# psu.net
KiCad netlist of a schematic drawn in EAGLE
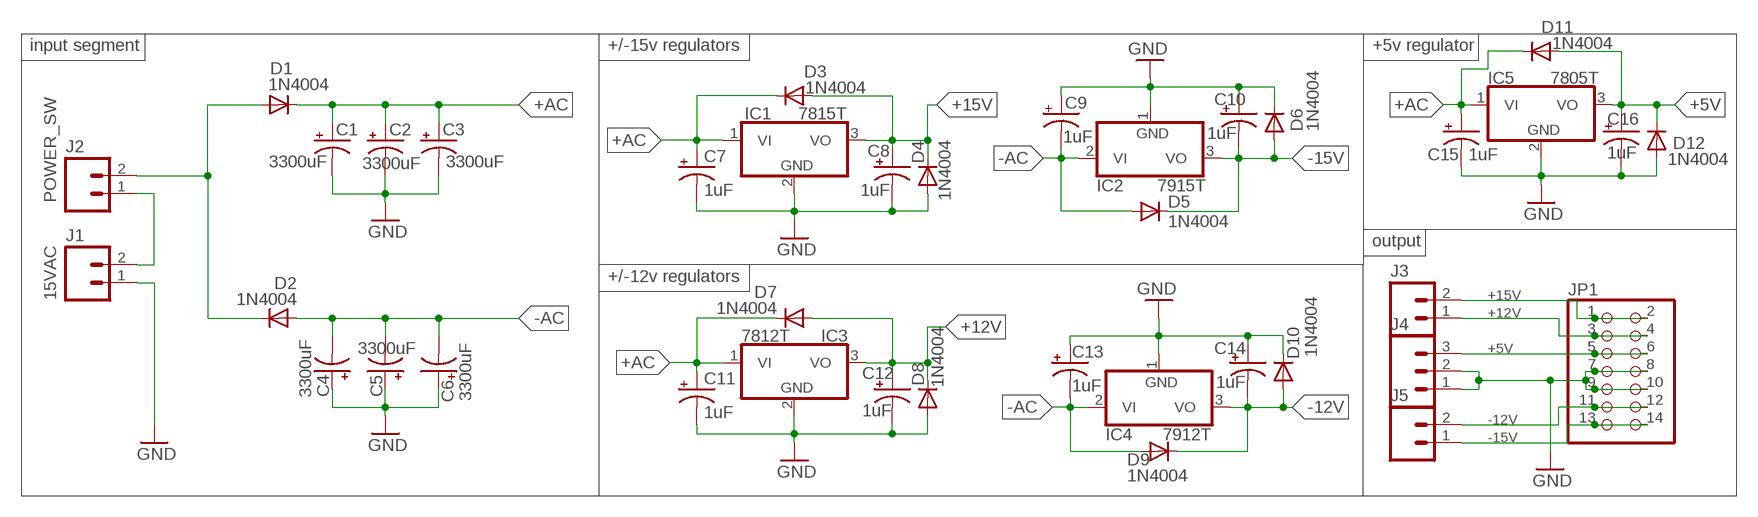
[diagram p0: schematic, sheet 1]

(export (version "E")
  (design (tool "Eeschema 10.0.6"))
  (components
    (comp (ref "C1")
      (value "3300uF")
      (footprint "eagle-import:E7,5-18")
      (libsource (lib "eagle-import") (part "CPOL-USE7.5-18"))
    )
    (comp (ref "C2")
      (value "3300uF")
      (footprint "eagle-import:E7,5-18")
      (libsource (lib "eagle-import") (part "CPOL-USE7.5-18"))
    )
    (comp (ref "C3")
      (value "3300uF")
      (footprint "eagle-import:E7,5-18")
      (libsource (lib "eagle-import") (part "CPOL-USE7.5-18"))
    )
    (comp (ref "C4")
      (value "3300uF")
      (footprint "eagle-import:E7,5-18")
      (libsource (lib "eagle-import") (part "CPOL-USE7.5-18"))
    )
    (comp (ref "C5")
      (value "3300uF")
      (footprint "eagle-import:E7,5-18")
      (libsource (lib "eagle-import") (part "CPOL-USE7.5-18"))
    )
    (comp (ref "C6")
      (value "3300uF")
      (footprint "eagle-import:E7,5-18")
      (libsource (lib "eagle-import") (part "CPOL-USE7.5-18"))
    )
    (comp (ref "C7")
      (value "1uF")
      (footprint "eagle-import:E2,5-5")
      (libsource (lib "eagle-import") (part "CPOL-USE2.5-5"))
    )
    (comp (ref "C8")
      (value "1uF")
      (footprint "eagle-import:E2,5-5")
      (libsource (lib "eagle-import") (part "CPOL-USE2.5-5"))
    )
    (comp (ref "C9")
      (value "1uF")
      (footprint "eagle-import:E2,5-5")
      (libsource (lib "eagle-import") (part "CPOL-USE2.5-5"))
    )
    (comp (ref "C10")
      (value "1uF")
      (footprint "eagle-import:E2,5-5")
      (libsource (lib "eagle-import") (part "CPOL-USE2.5-5"))
    )
    (comp (ref "C11")
      (value "1uF")
      (footprint "eagle-import:E2,5-5")
      (libsource (lib "eagle-import") (part "CPOL-USE2.5-5"))
    )
    (comp (ref "C12")
      (value "1uF")
      (footprint "eagle-import:E2,5-5")
      (libsource (lib "eagle-import") (part "CPOL-USE2.5-5"))
    )
    (comp (ref "C13")
      (value "1uF")
      (footprint "eagle-import:E2,5-5")
      (libsource (lib "eagle-import") (part "CPOL-USE2.5-5"))
    )
    (comp (ref "C14")
      (value "1uF")
      (footprint "eagle-import:E2,5-5")
      (libsource (lib "eagle-import") (part "CPOL-USE2.5-5"))
    )
    (comp (ref "C15")
      (value "1uF")
      (footprint "eagle-import:E2,5-5")
      (libsource (lib "eagle-import") (part "CPOL-USE2.5-5"))
    )
    (comp (ref "C16")
      (value "1uF")
      (footprint "eagle-import:E2,5-5")
      (libsource (lib "eagle-import") (part "CPOL-USE2.5-5"))
    )
    (comp (ref "D1")
      (value "1N4004")
      (footprint "eagle-import:DO41-10")
      (libsource (lib "eagle-import") (part "1N4004"))
    )
    (comp (ref "D2")
      (value "1N4004")
      (footprint "eagle-import:DO41-10")
      (libsource (lib "eagle-import") (part "1N4004"))
    )
    (comp (ref "D3")
      (value "1N4004")
      (footprint "eagle-import:DO41-10")
      (libsource (lib "eagle-import") (part "1N4004"))
    )
    (comp (ref "D4")
      (value "1N4004")
      (footprint "eagle-import:DO41-10")
      (libsource (lib "eagle-import") (part "1N4004"))
    )
    (comp (ref "D5")
      (value "1N4004")
      (footprint "eagle-import:DO41-10")
      (libsource (lib "eagle-import") (part "1N4004"))
    )
    (comp (ref "D6")
      (value "1N4004")
      (footprint "eagle-import:DO41-10")
      (libsource (lib "eagle-import") (part "1N4004"))
    )
    (comp (ref "D7")
      (value "1N4004")
      (footprint "eagle-import:DO41-10")
      (libsource (lib "eagle-import") (part "1N4004"))
    )
    (comp (ref "D8")
      (value "1N4004")
      (footprint "eagle-import:DO41-10")
      (libsource (lib "eagle-import") (part "1N4004"))
    )
    (comp (ref "D9")
      (value "1N4004")
      (footprint "eagle-import:DO41-10")
      (libsource (lib "eagle-import") (part "1N4004"))
    )
    (comp (ref "D10")
      (value "1N4004")
      (footprint "eagle-import:DO41-10")
      (libsource (lib "eagle-import") (part "1N4004"))
    )
    (comp (ref "D11")
      (value "1N4004")
      (footprint "eagle-import:DO41-10")
      (libsource (lib "eagle-import") (part "1N4004"))
    )
    (comp (ref "D12")
      (value "1N4004")
      (footprint "eagle-import:DO41-10")
      (libsource (lib "eagle-import") (part "1N4004"))
    )
    (comp (ref "IC1")
      (value "7815T")
      (footprint "eagle-import:TO220H")
      (libsource (lib "eagle-import") (part "78T15"))
    )
    (comp (ref "IC2")
      (value "7915T")
      (footprint "eagle-import:TO220H")
      (libsource (lib "eagle-import") (part "79T15"))
    )
    (comp (ref "IC3")
      (value "7812T")
      (footprint "eagle-import:TO220H")
      (libsource (lib "eagle-import") (part "78T12"))
    )
    (comp (ref "IC4")
      (value "7912T")
      (footprint "eagle-import:TO220H")
      (libsource (lib "eagle-import") (part "79T12"))
    )
    (comp (ref "IC5")
      (value "7805T")
      (footprint "eagle-import:TO220H")
      (libsource (lib "eagle-import") (part "78T05"))
    )
    (comp (ref "J1")
      (value "15VAC")
      (footprint "eagle-import:SCREWTERMINAL-5MM-2")
      (libsource (lib "eagle-import") (part "M025MM"))
    )
    (comp (ref "J2")
      (value "POWER_SW")
      (footprint "eagle-import:SCREWTERMINAL-5MM-2")
      (libsource (lib "eagle-import") (part "M025MM"))
    )
    (comp (ref "J3")
      (value "M025MM")
      (footprint "eagle-import:SCREWTERMINAL-5MM-2")
      (libsource (lib "eagle-import") (part "M025MM"))
    )
    (comp (ref "J4")
      (value "M03-SCREW-5MM")
      (footprint "eagle-import:SCREWTERMINAL-5MM-3")
      (libsource (lib "eagle-import") (part "M03-SCREW-5MM"))
    )
    (comp (ref "J5")
      (value "M025MM")
      (footprint "eagle-import:SCREWTERMINAL-5MM-2")
      (libsource (lib "eagle-import") (part "M025MM"))
    )
    (comp (ref "JP1")
      (value "PINHD-2X7")
      (footprint "eagle-import:2X07")
      (libsource (lib "eagle-import") (part "PINHD-2X7"))
    )
  )
  (nets
    (net (code "1") (name "+5V") (class "Default")
      (node (ref "C16") (pin "+") (pinfunction "+_+") (pintype "passive"))
      (node (ref "D11") (pin "A") (pinfunction "A_A") (pintype "passive"))
      (node (ref "D12") (pin "C") (pinfunction "C_C") (pintype "passive"))
      (node (ref "IC5") (pin "3") (pinfunction "VO_3") (pintype "passive"))
      (node (ref "J4") (pin "3") (pinfunction "3_3") (pintype "passive"))
      (node (ref "JP1") (pin "5") (pinfunction "5_5") (pintype "passive"))
      (node (ref "JP1") (pin "6") (pinfunction "6_6") (pintype "passive"))
    )
    (net (code "2") (name "+12V") (class "Default")
      (node (ref "C12") (pin "+") (pinfunction "+_+") (pintype "passive"))
      (node (ref "D7") (pin "A") (pinfunction "A_A") (pintype "passive"))
      (node (ref "D8") (pin "C") (pinfunction "C_C") (pintype "passive"))
      (node (ref "IC3") (pin "3") (pinfunction "VO_3") (pintype "passive"))
      (node (ref "J3") (pin "1") (pinfunction "1_1") (pintype "passive"))
      (node (ref "JP1") (pin "3") (pinfunction "3_3") (pintype "passive"))
      (node (ref "JP1") (pin "4") (pinfunction "4_4") (pintype "passive"))
    )
    (net (code "3") (name "+15V") (class "Default")
      (node (ref "C8") (pin "+") (pinfunction "+_+") (pintype "passive"))
      (node (ref "D3") (pin "A") (pinfunction "A_A") (pintype "passive"))
      (node (ref "D4") (pin "C") (pinfunction "C_C") (pintype "passive"))
      (node (ref "IC1") (pin "3") (pinfunction "VO_3") (pintype "passive"))
      (node (ref "J3") (pin "2") (pinfunction "2_2") (pintype "passive"))
      (node (ref "JP1") (pin "1") (pinfunction "1_1") (pintype "passive"))
      (node (ref "JP1") (pin "2") (pinfunction "2_2") (pintype "passive"))
    )
    (net (code "4") (name "+AC") (class "Default")
      (node (ref "C1") (pin "+") (pinfunction "+_+") (pintype "passive"))
      (node (ref "C11") (pin "+") (pinfunction "+_+") (pintype "passive"))
      (node (ref "C15") (pin "+") (pinfunction "+_+") (pintype "passive"))
      (node (ref "C2") (pin "+") (pinfunction "+_+") (pintype "passive"))
      (node (ref "C3") (pin "+") (pinfunction "+_+") (pintype "passive"))
      (node (ref "C7") (pin "+") (pinfunction "+_+") (pintype "passive"))
      (node (ref "D1") (pin "C") (pinfunction "C_C") (pintype "passive"))
      (node (ref "D11") (pin "C") (pinfunction "C_C") (pintype "passive"))
      (node (ref "D3") (pin "C") (pinfunction "C_C") (pintype "passive"))
      (node (ref "D7") (pin "C") (pinfunction "C_C") (pintype "passive"))
      (node (ref "IC1") (pin "1") (pinfunction "VI_1") (pintype "input"))
      (node (ref "IC3") (pin "1") (pinfunction "VI_1") (pintype "input"))
      (node (ref "IC5") (pin "1") (pinfunction "VI_1") (pintype "input"))
    )
    (net (code "5") (name "-12V") (class "Default")
      (node (ref "C14") (pin "-") (pinfunction "-_-") (pintype "passive"))
      (node (ref "D10") (pin "A") (pinfunction "A_A") (pintype "passive"))
      (node (ref "D9") (pin "C") (pinfunction "C_C") (pintype "passive"))
      (node (ref "IC4") (pin "3") (pinfunction "VO_3") (pintype "passive"))
      (node (ref "J5") (pin "2") (pinfunction "2_2") (pintype "passive"))
      (node (ref "JP1") (pin "11") (pinfunction "11_11") (pintype "passive"))
      (node (ref "JP1") (pin "12") (pinfunction "12_12") (pintype "passive"))
    )
    (net (code "6") (name "-15V") (class "Default")
      (node (ref "C10") (pin "-") (pinfunction "-_-") (pintype "passive"))
      (node (ref "D5") (pin "C") (pinfunction "C_C") (pintype "passive"))
      (node (ref "D6") (pin "A") (pinfunction "A_A") (pintype "passive"))
      (node (ref "IC2") (pin "3") (pinfunction "VO_3") (pintype "passive"))
      (node (ref "J5") (pin "1") (pinfunction "1_1") (pintype "passive"))
      (node (ref "JP1") (pin "13") (pinfunction "13_13") (pintype "passive"))
      (node (ref "JP1") (pin "14") (pinfunction "14_14") (pintype "passive"))
    )
    (net (code "7") (name "-AC") (class "Default")
      (node (ref "C13") (pin "-") (pinfunction "-_-") (pintype "passive"))
      (node (ref "C4") (pin "-") (pinfunction "-_-") (pintype "passive"))
      (node (ref "C5") (pin "-") (pinfunction "-_-") (pintype "passive"))
      (node (ref "C6") (pin "-") (pinfunction "-_-") (pintype "passive"))
      (node (ref "C9") (pin "-") (pinfunction "-_-") (pintype "passive"))
      (node (ref "D2") (pin "A") (pinfunction "A_A") (pintype "passive"))
      (node (ref "D5") (pin "A") (pinfunction "A_A") (pintype "passive"))
      (node (ref "D9") (pin "A") (pinfunction "A_A") (pintype "passive"))
      (node (ref "IC2") (pin "2") (pinfunction "VI_2") (pintype "input"))
      (node (ref "IC4") (pin "2") (pinfunction "VI_2") (pintype "input"))
    )
    (net (code "8") (name "GND") (class "Default")
      (node (ref "C1") (pin "-") (pinfunction "-_-") (pintype "passive"))
      (node (ref "C10") (pin "+") (pinfunction "+_+") (pintype "passive"))
      (node (ref "C11") (pin "-") (pinfunction "-_-") (pintype "passive"))
      (node (ref "C12") (pin "-") (pinfunction "-_-") (pintype "passive"))
      (node (ref "C13") (pin "+") (pinfunction "+_+") (pintype "passive"))
      (node (ref "C14") (pin "+") (pinfunction "+_+") (pintype "passive"))
      (node (ref "C15") (pin "-") (pinfunction "-_-") (pintype "passive"))
      (node (ref "C16") (pin "-") (pinfunction "-_-") (pintype "passive"))
      (node (ref "C2") (pin "-") (pinfunction "-_-") (pintype "passive"))
      (node (ref "C3") (pin "-") (pinfunction "-_-") (pintype "passive"))
      (node (ref "C4") (pin "+") (pinfunction "+_+") (pintype "passive"))
      (node (ref "C5") (pin "+") (pinfunction "+_+") (pintype "passive"))
      (node (ref "C6") (pin "+") (pinfunction "+_+") (pintype "passive"))
      (node (ref "C7") (pin "-") (pinfunction "-_-") (pintype "passive"))
      (node (ref "C8") (pin "-") (pinfunction "-_-") (pintype "passive"))
      (node (ref "C9") (pin "+") (pinfunction "+_+") (pintype "passive"))
      (node (ref "D10") (pin "C") (pinfunction "C_C") (pintype "passive"))
      (node (ref "D12") (pin "A") (pinfunction "A_A") (pintype "passive"))
      (node (ref "D4") (pin "A") (pinfunction "A_A") (pintype "passive"))
      (node (ref "D6") (pin "C") (pinfunction "C_C") (pintype "passive"))
      (node (ref "D8") (pin "A") (pinfunction "A_A") (pintype "passive"))
      (node (ref "IC1") (pin "2") (pinfunction "GND_2") (pintype "passive"))
      (node (ref "IC2") (pin "1") (pinfunction "GND_1") (pintype "passive"))
      (node (ref "IC3") (pin "2") (pinfunction "GND_2") (pintype "passive"))
      (node (ref "IC4") (pin "1") (pinfunction "GND_1") (pintype "passive"))
      (node (ref "IC5") (pin "2") (pinfunction "GND_2") (pintype "passive"))
      (node (ref "J1") (pin "1") (pinfunction "1_1") (pintype "passive"))
      (node (ref "J4") (pin "1") (pinfunction "1_1") (pintype "passive"))
      (node (ref "J4") (pin "2") (pinfunction "2_2") (pintype "passive"))
      (node (ref "JP1") (pin "10") (pinfunction "10_10") (pintype "passive"))
      (node (ref "JP1") (pin "7") (pinfunction "7_7") (pintype "passive"))
      (node (ref "JP1") (pin "8") (pinfunction "8_8") (pintype "passive"))
      (node (ref "JP1") (pin "9") (pinfunction "9_9") (pintype "passive"))
    )
    (net (code "9") (name "Net-(D1-PadA)") (class "Default")
      (node (ref "D1") (pin "A") (pinfunction "A_A") (pintype "passive"))
      (node (ref "D2") (pin "C") (pinfunction "C_C") (pintype "passive"))
      (node (ref "J2") (pin "2") (pinfunction "2_2") (pintype "passive"))
    )
    (net (code "10") (name "Net-(J1-Pad2)") (class "Default")
      (node (ref "J1") (pin "2") (pinfunction "2_2") (pintype "passive"))
      (node (ref "J2") (pin "1") (pinfunction "1_1") (pintype "passive"))
    )
  )
)
